# adc.net
KiCad netlist of a schematic drawn in EAGLE
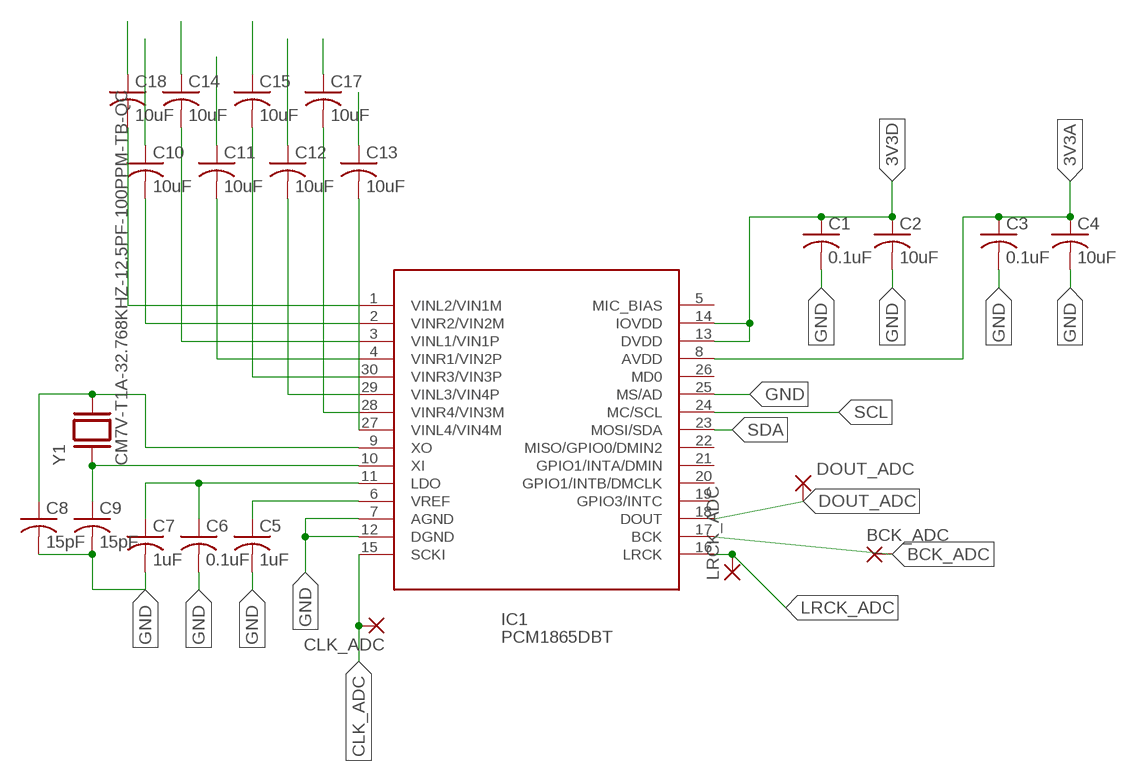
[diagram p0: schematic, sheet 1]

(export (version "E")
  (design (tool "Eeschema 10.0.6"))
  (components
    (comp (ref "BCK_ADC")
      (value "SMD2")
      (footprint "eagle-import:SMD1,27-2,54")
      (libsource (lib "eagle-import") (part "SMD2"))
    )
    (comp (ref "C1")
      (value "0.1uF")
      (footprint "eagle-import:C0402")
      (libsource (lib "eagle-import") (part "C-USC0402"))
    )
    (comp (ref "C2")
      (value "10uF")
      (footprint "eagle-import:C0402")
      (libsource (lib "eagle-import") (part "C-USC0402"))
    )
    (comp (ref "C3")
      (value "0.1uF")
      (footprint "eagle-import:C0402")
      (libsource (lib "eagle-import") (part "C-USC0402"))
    )
    (comp (ref "C4")
      (value "10uF")
      (footprint "eagle-import:C0402")
      (libsource (lib "eagle-import") (part "C-USC0402"))
    )
    (comp (ref "C5")
      (value "1uF")
      (footprint "eagle-import:C0402")
      (libsource (lib "eagle-import") (part "C-USC0402"))
    )
    (comp (ref "C6")
      (value "0.1uF")
      (footprint "eagle-import:C0402")
      (libsource (lib "eagle-import") (part "C-USC0402"))
    )
    (comp (ref "C7")
      (value "1uF")
      (footprint "eagle-import:C0402")
      (libsource (lib "eagle-import") (part "C-USC0402"))
    )
    (comp (ref "C8")
      (value "15pF")
      (footprint "eagle-import:C0402")
      (libsource (lib "eagle-import") (part "C-USC0402"))
    )
    (comp (ref "C9")
      (value "15pF")
      (footprint "eagle-import:C0402")
      (libsource (lib "eagle-import") (part "C-USC0402"))
    )
    (comp (ref "C10")
      (value "10uF")
      (footprint "eagle-import:C0402")
      (libsource (lib "eagle-import") (part "C-USC0402"))
    )
    (comp (ref "C11")
      (value "10uF")
      (footprint "eagle-import:C0402")
      (libsource (lib "eagle-import") (part "C-USC0402"))
    )
    (comp (ref "C12")
      (value "10uF")
      (footprint "eagle-import:C0402")
      (libsource (lib "eagle-import") (part "C-USC0402"))
    )
    (comp (ref "C13")
      (value "10uF")
      (footprint "eagle-import:C0402")
      (libsource (lib "eagle-import") (part "C-USC0402"))
    )
    (comp (ref "C14")
      (value "10uF")
      (footprint "eagle-import:C0402")
      (libsource (lib "eagle-import") (part "C-USC0402"))
    )
    (comp (ref "C15")
      (value "10uF")
      (footprint "eagle-import:C0402")
      (libsource (lib "eagle-import") (part "C-USC0402"))
    )
    (comp (ref "C17")
      (value "10uF")
      (footprint "eagle-import:C0402")
      (libsource (lib "eagle-import") (part "C-USC0402"))
    )
    (comp (ref "C18")
      (value "10uF")
      (footprint "eagle-import:C0402")
      (libsource (lib "eagle-import") (part "C-USC0402"))
    )
    (comp (ref "CLK_ADC")
      (value "SMD2")
      (footprint "eagle-import:SMD1,27-2,54")
      (libsource (lib "eagle-import") (part "SMD2"))
    )
    (comp (ref "DOUT_ADC")
      (value "SMD2")
      (footprint "eagle-import:SMD1,27-2,54")
      (libsource (lib "eagle-import") (part "SMD2"))
    )
    (comp (ref "IC1")
      (value "PCM1865DBT")
      (footprint "eagle-import:TSSOP-30")
      (fields (field (name "MF") "Texas Instruments"))
      (libsource (lib "eagle-import") (part "PCM1865DBT"))
    )
    (comp (ref "LRCK_ADC")
      (value "SMD2")
      (footprint "eagle-import:SMD1,27-2,54")
      (libsource (lib "eagle-import") (part "SMD2"))
    )
    (comp (ref "Y1")
      (value "CM7V-T1A-32.768KHZ-12.5PF-100PPM-TB-QC")
      (footprint "eagle-import:XTAL_CM7V-T1A-32.768KHZ-12.5PF-100PPM-TB-QC")
      (fields
        (field (name "MF") "Micro Crystal")
        (field (name "MP") "CM7V-T1A-32.768kHz-12.5pF-100PPM-TB-QC")
      )
      (libsource (lib "eagle-import") (part "CM7V-T1A-32.768KHZ-12.5PF-100PPM-TB-QC"))
    )
  )
  (nets
    (net (code "1") (name "3V3A") (class "Default")
      (node (ref "C3") (pin "1") (pinfunction "1_1") (pintype "passive"))
      (node (ref "C4") (pin "1") (pinfunction "1_1") (pintype "passive"))
      (node (ref "IC1") (pin "8") (pinfunction "AVDD_8") (pintype "bidirectional"))
    )
    (net (code "2") (name "3V3D") (class "Default")
      (node (ref "C1") (pin "1") (pinfunction "1_1") (pintype "passive"))
      (node (ref "C2") (pin "1") (pinfunction "1_1") (pintype "passive"))
      (node (ref "IC1") (pin "13") (pinfunction "DVDD_13") (pintype "bidirectional"))
      (node (ref "IC1") (pin "14") (pinfunction "IOVDD_14") (pintype "bidirectional"))
    )
    (net (code "3") (name "BCK_ADC") (class "Default")
      (node (ref "BCK_ADC") (pin "1") (pinfunction "P_1") (pintype "passive"))
      (node (ref "IC1") (pin "17") (pinfunction "BCK_17") (pintype "bidirectional"))
    )
    (net (code "4") (name "CLK_ADC") (class "Default")
      (node (ref "CLK_ADC") (pin "1") (pinfunction "P_1") (pintype "passive"))
      (node (ref "IC1") (pin "15") (pinfunction "SCKI_15") (pintype "bidirectional"))
    )
    (net (code "5") (name "DOUT_ADC") (class "Default")
      (node (ref "DOUT_ADC") (pin "1") (pinfunction "P_1") (pintype "passive"))
      (node (ref "IC1") (pin "18") (pinfunction "DOUT_18") (pintype "bidirectional"))
    )
    (net (code "6") (name "GND") (class "Default")
      (node (ref "C1") (pin "2") (pinfunction "2_2") (pintype "passive"))
      (node (ref "C2") (pin "2") (pinfunction "2_2") (pintype "passive"))
      (node (ref "C3") (pin "2") (pinfunction "2_2") (pintype "passive"))
      (node (ref "C4") (pin "2") (pinfunction "2_2") (pintype "passive"))
      (node (ref "C5") (pin "2") (pinfunction "2_2") (pintype "passive"))
      (node (ref "C6") (pin "2") (pinfunction "2_2") (pintype "passive"))
      (node (ref "C7") (pin "2") (pinfunction "2_2") (pintype "passive"))
      (node (ref "C8") (pin "2") (pinfunction "2_2") (pintype "passive"))
      (node (ref "C9") (pin "2") (pinfunction "2_2") (pintype "passive"))
      (node (ref "IC1") (pin "12") (pinfunction "DGND_12") (pintype "bidirectional"))
      (node (ref "IC1") (pin "25") (pinfunction "MS/AD_25") (pintype "bidirectional"))
      (node (ref "IC1") (pin "7") (pinfunction "AGND_7") (pintype "bidirectional"))
    )
    (net (code "7") (name "LRCK_ADC") (class "Default")
      (node (ref "IC1") (pin "16") (pinfunction "LRCK_16") (pintype "bidirectional"))
      (node (ref "LRCK_ADC") (pin "1") (pinfunction "P_1") (pintype "passive"))
    )
    (net (code "8") (name "Net-(IC1-LDO)") (class "Default")
      (node (ref "C6") (pin "1") (pinfunction "1_1") (pintype "passive"))
      (node (ref "C7") (pin "1") (pinfunction "1_1") (pintype "passive"))
      (node (ref "IC1") (pin "11") (pinfunction "LDO_11") (pintype "bidirectional"))
    )
    (net (code "9") (name "Net-(IC1-VINL1{slash}VIN1P)") (class "Default")
      (node (ref "C14") (pin "2") (pinfunction "2_2") (pintype "passive"))
      (node (ref "IC1") (pin "3") (pinfunction "VINL1/VIN1P_3") (pintype "bidirectional"))
    )
    (net (code "10") (name "Net-(IC1-VINL2{slash}VIN1M)") (class "Default")
      (node (ref "C18") (pin "2") (pinfunction "2_2") (pintype "passive"))
      (node (ref "IC1") (pin "1") (pinfunction "VINL2/VIN1M_1") (pintype "bidirectional"))
    )
    (net (code "11") (name "Net-(IC1-VINL3{slash}VIN4P)") (class "Default")
      (node (ref "C12") (pin "2") (pinfunction "2_2") (pintype "passive"))
      (node (ref "IC1") (pin "29") (pinfunction "VINL3/VIN4P_29") (pintype "bidirectional"))
    )
    (net (code "12") (name "Net-(IC1-VINL4{slash}VIN4M)") (class "Default")
      (node (ref "C13") (pin "2") (pinfunction "2_2") (pintype "passive"))
      (node (ref "IC1") (pin "27") (pinfunction "VINL4/VIN4M_27") (pintype "bidirectional"))
    )
    (net (code "13") (name "Net-(IC1-VINR1{slash}VIN2P)") (class "Default")
      (node (ref "C11") (pin "2") (pinfunction "2_2") (pintype "passive"))
      (node (ref "IC1") (pin "4") (pinfunction "VINR1/VIN2P_4") (pintype "bidirectional"))
    )
    (net (code "14") (name "Net-(IC1-VINR2{slash}VIN2M)") (class "Default")
      (node (ref "C10") (pin "2") (pinfunction "2_2") (pintype "passive"))
      (node (ref "IC1") (pin "2") (pinfunction "VINR2/VIN2M_2") (pintype "bidirectional"))
    )
    (net (code "15") (name "Net-(IC1-VINR3{slash}VIN3P)") (class "Default")
      (node (ref "C15") (pin "2") (pinfunction "2_2") (pintype "passive"))
      (node (ref "IC1") (pin "30") (pinfunction "VINR3/VIN3P_30") (pintype "bidirectional"))
    )
    (net (code "16") (name "Net-(IC1-VINR4{slash}VIN3M)") (class "Default")
      (node (ref "C17") (pin "2") (pinfunction "2_2") (pintype "passive"))
      (node (ref "IC1") (pin "28") (pinfunction "VINR4/VIN3M_28") (pintype "bidirectional"))
    )
    (net (code "17") (name "Net-(IC1-VREF)") (class "Default")
      (node (ref "C5") (pin "1") (pinfunction "1_1") (pintype "passive"))
      (node (ref "IC1") (pin "6") (pinfunction "VREF_6") (pintype "bidirectional"))
    )
    (net (code "18") (name "Net-(IC1-XI)") (class "Default")
      (node (ref "C9") (pin "1") (pinfunction "1_1") (pintype "passive"))
      (node (ref "IC1") (pin "10") (pinfunction "XI_10") (pintype "bidirectional"))
      (node (ref "Y1") (pin "1") (pinfunction "1_1") (pintype "passive"))
    )
    (net (code "19") (name "Net-(IC1-XO)") (class "Default")
      (node (ref "C8") (pin "1") (pinfunction "1_1") (pintype "passive"))
      (node (ref "IC1") (pin "9") (pinfunction "XO_9") (pintype "bidirectional"))
      (node (ref "Y1") (pin "2") (pinfunction "2_2") (pintype "passive"))
    )
    (net (code "20") (name "SCL") (class "Default")
      (node (ref "IC1") (pin "24") (pinfunction "MC/SCL_24") (pintype "bidirectional"))
    )
    (net (code "21") (name "SDA") (class "Default")
      (node (ref "IC1") (pin "23") (pinfunction "MOSI/SDA_23") (pintype "bidirectional"))
    )
    (net (code "22") (name "unconnected-(C10-Pad1)") (class "Default")
      (node (ref "C10") (pin "1") (pinfunction "1_1") (pintype "passive"))
    )
    (net (code "23") (name "unconnected-(C11-Pad1)") (class "Default")
      (node (ref "C11") (pin "1") (pinfunction "1_1") (pintype "passive"))
    )
    (net (code "24") (name "unconnected-(C12-Pad1)") (class "Default")
      (node (ref "C12") (pin "1") (pinfunction "1_1") (pintype "passive"))
    )
    (net (code "25") (name "unconnected-(C13-Pad1)") (class "Default")
      (node (ref "C13") (pin "1") (pinfunction "1_1") (pintype "passive"))
    )
    (net (code "26") (name "unconnected-(C14-Pad1)") (class "Default")
      (node (ref "C14") (pin "1") (pinfunction "1_1") (pintype "passive"))
    )
    (net (code "27") (name "unconnected-(C15-Pad1)") (class "Default")
      (node (ref "C15") (pin "1") (pinfunction "1_1") (pintype "passive"))
    )
    (net (code "28") (name "unconnected-(C17-Pad1)") (class "Default")
      (node (ref "C17") (pin "1") (pinfunction "1_1") (pintype "passive"))
    )
    (net (code "29") (name "unconnected-(C18-Pad1)") (class "Default")
      (node (ref "C18") (pin "1") (pinfunction "1_1") (pintype "passive"))
    )
    (net (code "30") (name "unconnected-(IC1-GPIO1{slash}INTA{slash}DMIN-Pad21)") (class "Default")
      (node (ref "IC1") (pin "21") (pinfunction "GPIO1/INTA/DMIN_21") (pintype "bidirectional"))
    )
    (net (code "31") (name "unconnected-(IC1-GPIO1{slash}INTB{slash}DMCLK-Pad20)") (class "Default")
      (node (ref "IC1") (pin "20") (pinfunction "GPIO1/INTB/DMCLK_20") (pintype "bidirectional"))
    )
    (net (code "32") (name "unconnected-(IC1-GPIO3{slash}INTC-Pad19)") (class "Default")
      (node (ref "IC1") (pin "19") (pinfunction "GPIO3/INTC_19") (pintype "bidirectional"))
    )
    (net (code "33") (name "unconnected-(IC1-MD0-Pad26)") (class "Default")
      (node (ref "IC1") (pin "26") (pinfunction "MD0_26") (pintype "bidirectional"))
    )
    (net (code "34") (name "unconnected-(IC1-MIC_BIAS-Pad5)") (class "Default")
      (node (ref "IC1") (pin "5") (pinfunction "MIC_BIAS_5") (pintype "bidirectional"))
    )
    (net (code "35") (name "unconnected-(IC1-MISO{slash}GPIO0{slash}DMIN2-Pad22)") (class "Default")
      (node (ref "IC1") (pin "22") (pinfunction "MISO/GPIO0/DMIN2_22") (pintype "bidirectional"))
    )
  )
)
